# PowerUnit.net
KiCad netlist of a schematic drawn in Altium Designer
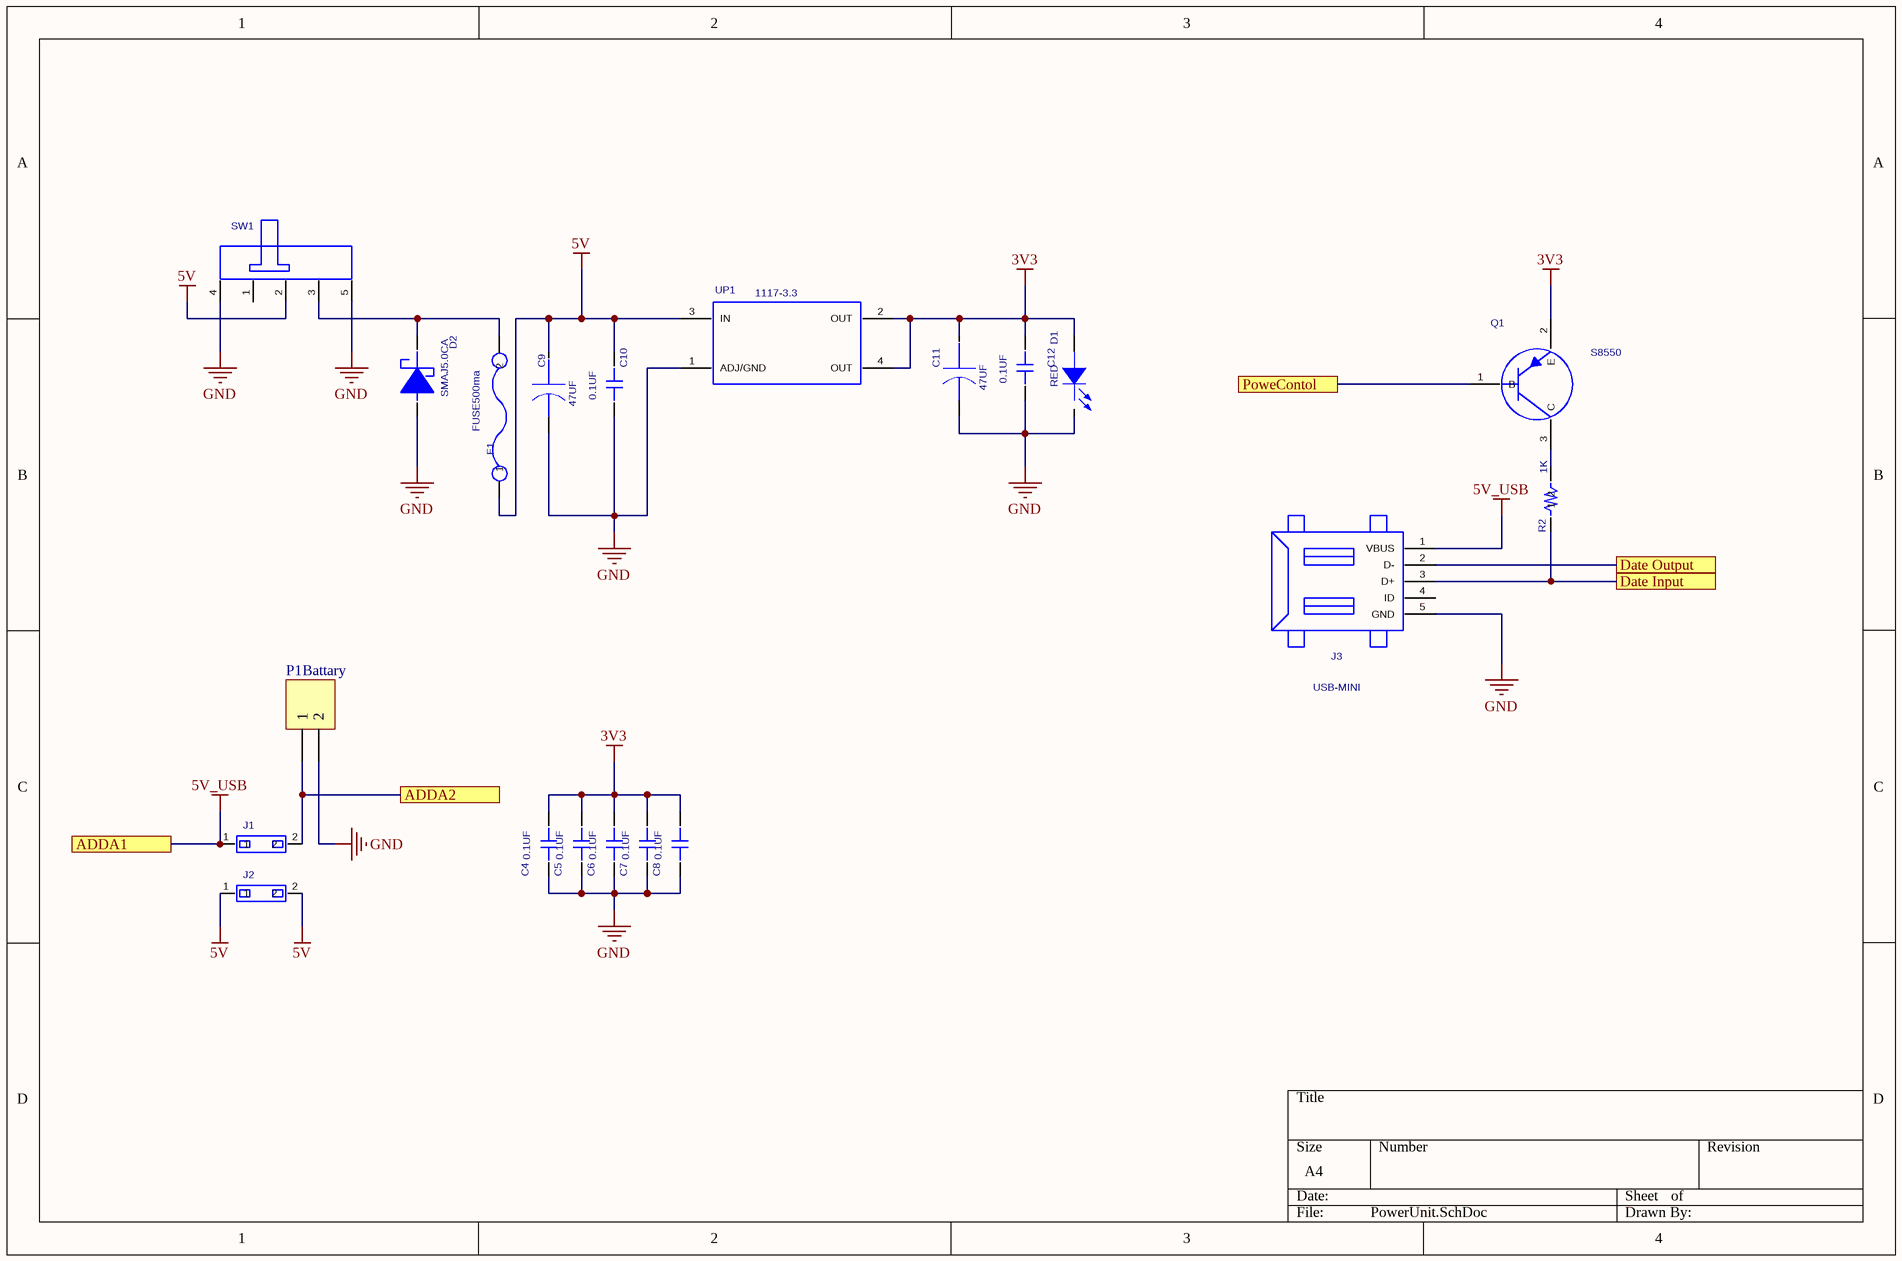
[diagram p0: PowerUnit.SchDoc]

(export (version "E")
  (design (tool "Eeschema 10.0.6"))
  (components
    (comp (ref "C4")
      (value "0.1UF")
      (footprint "CAP_0603_FIRE")
      (description "SURFACE MOUNT CAPACITOR 0.031 X 0.061 INCHES")
      (fields (field (name "Comment") "CAP_0.1UF_0603_FIRE"))
      (libsource (lib "MINI-V3") (part "CAP_0.1UF_0603_FIRE"))
    )
    (comp (ref "C5")
      (value "0.1UF")
      (footprint "CAP_0603_FIRE")
      (description "SURFACE MOUNT CAPACITOR 0.031 X 0.061 INCHES")
      (fields (field (name "Comment") "CAP_0.1UF_0603_FIRE"))
      (libsource (lib "MINI-V3") (part "CAP_0.1UF_0603_FIRE"))
    )
    (comp (ref "C6")
      (value "0.1UF")
      (footprint "CAP_0603_FIRE")
      (description "SURFACE MOUNT CAPACITOR 0.031 X 0.061 INCHES")
      (fields (field (name "Comment") "CAP_0.1UF_0603_FIRE"))
      (libsource (lib "MINI-V3") (part "CAP_0.1UF_0603_FIRE"))
    )
    (comp (ref "C7")
      (value "0.1UF")
      (footprint "CAP_0603_FIRE")
      (description "SURFACE MOUNT CAPACITOR 0.031 X 0.061 INCHES")
      (fields (field (name "Comment") "CAP_0.1UF_0603_FIRE"))
      (libsource (lib "MINI-V3") (part "CAP_0.1UF_0603_FIRE"))
    )
    (comp (ref "C8")
      (value "0.1UF")
      (footprint "CAP_0603_FIRE")
      (description "SURFACE MOUNT CAPACITOR 0.031 X 0.061 INCHES")
      (fields (field (name "Comment") "CAP_0.1UF_0603_FIRE"))
      (libsource (lib "MINI-V3") (part "CAP_0.1UF_0603_FIRE"))
    )
    (comp (ref "C9")
      (value "47UF")
      (footprint "CAP+_47UF_FIRE")
      (fields (field (name "Comment") "CAP+_47UF_FIRE"))
      (libsource (lib "MINI-V3") (part "CAP+_47UF_FIRE"))
    )
    (comp (ref "C10")
      (value "0.1UF")
      (footprint "CAP_0603_FIRE")
      (description "SURFACE MOUNT CAPACITOR 0.031 X 0.061 INCHES")
      (fields (field (name "Comment") "CAP_0.1UF_0603_FIRE"))
      (libsource (lib "MINI-V3") (part "CAP_0.1UF_0603_FIRE"))
    )
    (comp (ref "C11")
      (value "47UF")
      (footprint "CAP+_47UF_FIRE")
      (fields (field (name "Comment") "CAP+_47UF_FIRE"))
      (libsource (lib "MINI-V3") (part "CAP+_47UF_FIRE"))
    )
    (comp (ref "C12")
      (value "0.1UF")
      (footprint "CAP_0603_FIRE")
      (description "SURFACE MOUNT CAPACITOR 0.031 X 0.061 INCHES")
      (fields (field (name "Comment") "CAP_0.1UF_0603_FIRE"))
      (libsource (lib "MINI-V3") (part "CAP_0.1UF_0603_FIRE"))
    )
    (comp (ref "D1")
      (value "RED")
      (footprint "LED_RED_0603_FIRE")
      (description "red,0805")
      (fields (field (name "Comment") "LED_RED_0603_FIRE"))
      (libsource (lib "MINI-V3") (part "LED_RED_0603_FIRE"))
    )
    (comp (ref "D2") (value "SMAJ5.0CA") (footprint "DO-214") (libsource (lib "MINI-V3") (part "SMAJ5.0CA")))
    (comp (ref "F1")
      (value "FUSE500ma")
      (footprint "C1812")
      (fields (field (name "Comment") "FUSE500MA"))
      (libsource (lib "MINI-V3") (part "FUSE500MA"))
    )
    (comp (ref "J1")
      (value "1X2PIN_SMD")
      (footprint "1X2PIN_SMD")
      (libsource (lib "MINI-V3") (part "1X2PIN_SMD"))
    )
    (comp (ref "J2")
      (value "1X2PIN_SMD")
      (footprint "1X2PIN_SMD")
      (libsource (lib "MINI-V3") (part "1X2PIN_SMD"))
    )
    (comp (ref "J3") (value "USB-MINI") (footprint "USB-MINI") (libsource (lib "MINI-V3") (part "USB-MINI")))
    (comp (ref "P1")
      (value "Battary")
      (footprint "HDR1X2")
      (description "Header, 2-Pin")
      (fields (field (name "PUBLISHER") "Altium Limited"))
      (libsource (lib "插针") (part "Header 2"))
    )
    (comp (ref "Q1")
      (value "S8550")
      (footprint "SOT-23")
      (description "NPN")
      (libsource (lib "MINI-V3") (part "S8550"))
    )
    (comp (ref "R2")
      (value "1K")
      (footprint "RES_0603_FIRE")
      (description "0402")
      (fields (field (name "TOLERANCE") "+-5%") (field (name "Comment") "RES_1K_0603_FIRE"))
      (libsource (lib "MINI-V3") (part "RES_1K_0603_FIRE"))
    )
    (comp (ref "SW1")
      (value "SW-POWER")
      (footprint "SW13_6")
      (description "SW-5")
      (libsource (lib "MINI-V3") (part "SW-POWER"))
    )
    (comp (ref "UP1")
      (value "1117-3.3")
      (description "SOT-223")
      (libsource (lib "MINI-V3") (part "1117-3.3"))
    )
  )
  (nets
    (net (code "1") (name "/ADDA2") (class "Default")
      (node (ref "J1") (pin "2") (pinfunction "2_2") (pintype "passive"))
      (node (ref "P1") (pin "1") (pinfunction "1_1") (pintype "passive"))
    )
    (net (code "2") (name "/Date Input") (class "Default")
      (node (ref "J3") (pin "3") (pinfunction "D+_3") (pintype "passive"))
      (node (ref "R2") (pin "1") (pinfunction "1_1") (pintype "passive"))
    )
    (net (code "3") (name "/Date Output") (class "Default")
      (node (ref "J3") (pin "2") (pinfunction "D-_2") (pintype "passive"))
    )
    (net (code "4") (name "/PoweContol") (class "Default")
      (node (ref "Q1") (pin "1") (pinfunction "B_1") (pintype "passive"))
    )
    (net (code "5") (name "3V3") (class "Default")
      (node (ref "C11") (pin "1") (pinfunction "1_1") (pintype "passive"))
      (node (ref "C12") (pin "2") (pinfunction "2_2") (pintype "passive"))
      (node (ref "C4") (pin "2") (pinfunction "2_2") (pintype "passive"))
      (node (ref "C5") (pin "2") (pinfunction "2_2") (pintype "passive"))
      (node (ref "C6") (pin "2") (pinfunction "2_2") (pintype "passive"))
      (node (ref "C7") (pin "2") (pinfunction "2_2") (pintype "passive"))
      (node (ref "C8") (pin "2") (pinfunction "2_2") (pintype "passive"))
      (node (ref "D1") (pin "A") (pinfunction "ANODE_A") (pintype "passive"))
      (node (ref "Q1") (pin "2") (pinfunction "E_2") (pintype "passive"))
      (node (ref "UP1") (pin "2") (pinfunction "OUT_2") (pintype "passive"))
      (node (ref "UP1") (pin "4") (pinfunction "OUT_4") (pintype "passive"))
    )
    (net (code "6") (name "5V") (class "Default")
      (node (ref "C10") (pin "2") (pinfunction "2_2") (pintype "passive"))
      (node (ref "C9") (pin "1") (pinfunction "1_1") (pintype "passive"))
      (node (ref "F1") (pin "1") (pinfunction "1_1") (pintype "passive"))
      (node (ref "J2") (pin "1") (pinfunction "1_1") (pintype "passive"))
      (node (ref "J2") (pin "2") (pinfunction "2_2") (pintype "passive"))
      (node (ref "SW1") (pin "2") (pinfunction "2_2") (pintype "passive"))
      (node (ref "UP1") (pin "3") (pinfunction "IN_3") (pintype "passive"))
    )
    (net (code "7") (name "5V_USB") (class "Default")
      (node (ref "J1") (pin "1") (pinfunction "1_1") (pintype "passive"))
      (node (ref "J3") (pin "1") (pinfunction "VBUS_1") (pintype "passive"))
    )
    (net (code "8") (name "GND") (class "Default")
      (node (ref "C10") (pin "1") (pinfunction "1_1") (pintype "passive"))
      (node (ref "C11") (pin "2") (pinfunction "2_2") (pintype "passive"))
      (node (ref "C12") (pin "1") (pinfunction "1_1") (pintype "passive"))
      (node (ref "C4") (pin "1") (pinfunction "1_1") (pintype "passive"))
      (node (ref "C5") (pin "1") (pinfunction "1_1") (pintype "passive"))
      (node (ref "C6") (pin "1") (pinfunction "1_1") (pintype "passive"))
      (node (ref "C7") (pin "1") (pinfunction "1_1") (pintype "passive"))
      (node (ref "C8") (pin "1") (pinfunction "1_1") (pintype "passive"))
      (node (ref "C9") (pin "2") (pinfunction "2_2") (pintype "passive"))
      (node (ref "D1") (pin "K") (pinfunction "CATHODE_K") (pintype "passive"))
      (node (ref "D2") (pin "1") (pinfunction "+_1") (pintype "passive"))
      (node (ref "J3") (pin "5") (pinfunction "GND_5") (pintype "passive"))
      (node (ref "P1") (pin "2") (pinfunction "2_2") (pintype "passive"))
      (node (ref "SW1") (pin "4") (pinfunction "4_4") (pintype "passive"))
      (node (ref "SW1") (pin "5") (pinfunction "5_5") (pintype "passive"))
      (node (ref "UP1") (pin "1") (pinfunction "ADJ/GND_1") (pintype "passive"))
    )
    (net (code "9") (name "Net-(D2--)") (class "Default")
      (node (ref "D2") (pin "2") (pinfunction "-_2") (pintype "passive"))
      (node (ref "F1") (pin "2") (pinfunction "2_2") (pintype "passive"))
      (node (ref "SW1") (pin "3") (pinfunction "3_3") (pintype "passive"))
    )
    (net (code "10") (name "Net-(Q1-C)") (class "Default")
      (node (ref "Q1") (pin "3") (pinfunction "C_3") (pintype "passive"))
      (node (ref "R2") (pin "2") (pinfunction "2_2") (pintype "passive"))
    )
    (net (code "11") (name "unconnected-(J3-ID-Pad4)") (class "Default")
      (node (ref "J3") (pin "4") (pinfunction "ID_4") (pintype "passive"))
    )
    (net (code "12") (name "unconnected-(SW1-Pad1)") (class "Default")
      (node (ref "SW1") (pin "1") (pinfunction "1_1") (pintype "passive"))
    )
  )
)
